# tuch-tara-smd.net
KiCad netlist of a schematic drawn in Altium Designer
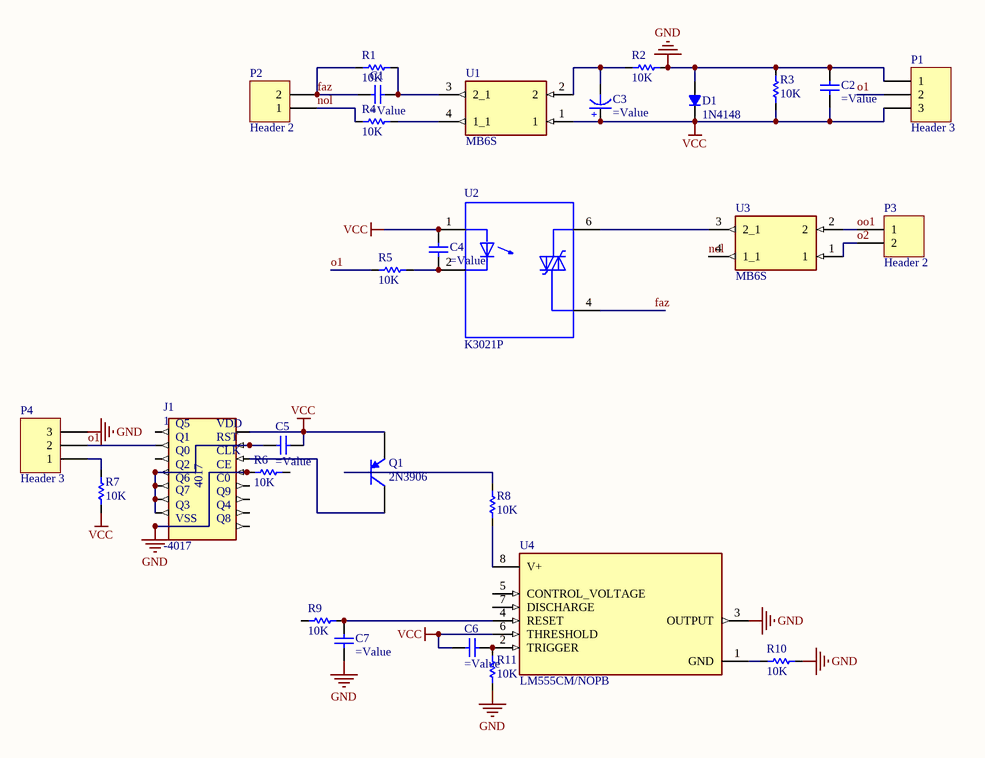
[diagram p0: tuch-tara-smd.SchDoc]

(export (version "E")
  (design (tool "Eeschema 10.0.6"))
  (components
    (comp (ref "C1")
      (value "~")
      (footprint "CAP-30")
      (description "Capacitor")
      (libsource (lib "AltiumLib1") (part "Capacitor"))
    )
    (comp (ref "C2")
      (value "~")
      (footprint "CAP 1206")
      (description "Capacitor")
      (libsource (lib "AltiumLib1") (part "Capacitor"))
    )
    (comp (ref "C3")
      (value "~")
      (footprint "ELEC-CAP-RAD10-20")
      (description "Electrolytic Capacitor")
      (libsource (lib "AltiumLib1") (part "Capacitor Electrolytic"))
    )
    (comp (ref "C4")
      (value "~")
      (footprint "CAP 1206")
      (description "Capacitor")
      (libsource (lib "AltiumLib1") (part "Capacitor"))
    )
    (comp (ref "C5")
      (value "~")
      (footprint "CAP 1206")
      (description "Capacitor")
      (libsource (lib "AltiumLib1") (part "Capacitor"))
    )
    (comp (ref "C6")
      (value "~")
      (footprint "CAP 1206")
      (description "Capacitor")
      (libsource (lib "AltiumLib1") (part "Capacitor"))
    )
    (comp (ref "C7")
      (value "~")
      (footprint "CAP 1206")
      (description "Capacitor")
      (libsource (lib "AltiumLib1") (part "Capacitor"))
    )
    (comp (ref "D1")
      (value "MODEL")
      (footprint "DO-41")
      (description "Diode")
      (fields (field (name "MODEL") "1N4148"))
      (libsource (lib "AltiumLib1") (part "Diode"))
    )
    (comp (ref "J1")
      (value "-4017")
      (footprint "SOIC127P600X175-16N")
      (description "10000pF Â±1% 25V Ceramic Capacitor C0G, NP0 0603 (1608 Metric)")
      (fields (field (name "MF") "Heyco") (field (name "MP") "4017"))
      (libsource (lib "-4017") (part "-4017"))
    )
    (comp (ref "P1")
      (value "Header 3")
      (footprint "HDR1X3")
      (description "Header, 3-Pin")
      (fields (field (name "PUBLISHER") "Altium Limited"))
      (libsource (lib "") (part "Header 3_1"))
    )
    (comp (ref "P2")
      (value "Header 2")
      (footprint "HDR1X2")
      (description "Header, 2-Pin")
      (fields (field (name "PUBLISHER") "Altium Limited"))
      (libsource (lib "") (part "Header 2_1"))
    )
    (comp (ref "P3")
      (value "Header 2")
      (footprint "HDR1X2")
      (description "Header, 2-Pin")
      (fields (field (name "PUBLISHER") "Altium Limited"))
      (libsource (lib "Miscellaneous Connectors") (part "Header 2"))
    )
    (comp (ref "P4")
      (value "Header 3")
      (footprint "HDR1X3")
      (description "Header, 3-Pin")
      (fields (field (name "PUBLISHER") "Altium Limited"))
      (libsource (lib "Miscellaneous Connectors") (part "Header 3"))
    )
    (comp (ref "Q1")
      (value "2N3906")
      (footprint "MMBT3904-TP:SOT23-3")
      (description "PNP General Purpose Amplifier")
      (fields (field (name "PUBLISHER") "Altium Limited"))
      (libsource (lib "Miscellaneous Devices") (part "2N3906"))
    )
    (comp (ref "R1")
      (value "10K")
      (footprint "RES 1206 (3216X08L)")
      (description "Resistor")
      (fields (field (name "TOLERANCE") "5%") (field (name "POWER") "1/4 W"))
      (libsource (lib "AltiumLib1") (part "Resistor"))
    )
    (comp (ref "R2")
      (value "10K")
      (footprint "RES 1206 (3216X08L)")
      (description "Resistor")
      (fields (field (name "TOLERANCE") "5%") (field (name "POWER") "1/4 W"))
      (libsource (lib "AltiumLib1") (part "Resistor"))
    )
    (comp (ref "R3")
      (value "10K")
      (footprint "RES 1206 (3216X08L)")
      (description "Resistor")
      (fields (field (name "TOLERANCE") "5%") (field (name "POWER") "1/4 W"))
      (libsource (lib "AltiumLib1") (part "Resistor"))
    )
    (comp (ref "R4")
      (value "10K")
      (footprint "RES 2512 (6331X07L)")
      (description "Resistor")
      (fields (field (name "TOLERANCE") "5%") (field (name "POWER") "1/4 W"))
      (libsource (lib "AltiumLib1") (part "Resistor"))
    )
    (comp (ref "R5")
      (value "10K")
      (footprint "RES 1206 (3216X08L)")
      (description "Resistor")
      (fields (field (name "TOLERANCE") "5%") (field (name "POWER") "1/4 W"))
      (libsource (lib "AltiumLib1") (part "Resistor"))
    )
    (comp (ref "R6")
      (value "10K")
      (footprint "RES 1206 (3216X08L)")
      (description "Resistor")
      (fields (field (name "TOLERANCE") "5%") (field (name "POWER") "1/4 W"))
      (libsource (lib "AltiumLib1") (part "Resistor"))
    )
    (comp (ref "R7")
      (value "10K")
      (footprint "Res-(1/4)")
      (description "Resistor")
      (fields (field (name "TOLERANCE") "5%") (field (name "POWER") "1/4 W"))
      (libsource (lib "AltiumLib1") (part "Resistor"))
    )
    (comp (ref "R8")
      (value "10K")
      (footprint "RES 1206 (3216X08L)")
      (description "Resistor")
      (fields (field (name "TOLERANCE") "5%") (field (name "POWER") "1/4 W"))
      (libsource (lib "AltiumLib1") (part "Resistor"))
    )
    (comp (ref "R9")
      (value "10K")
      (footprint "RES 1206 (3216X08L)")
      (description "Resistor")
      (fields (field (name "TOLERANCE") "5%") (field (name "POWER") "1/4 W"))
      (libsource (lib "AltiumLib1") (part "Resistor"))
    )
    (comp (ref "R10")
      (value "10K")
      (footprint "RES 1206 (3216X08L)")
      (description "Resistor")
      (fields (field (name "TOLERANCE") "5%") (field (name "POWER") "1/4 W"))
      (libsource (lib "AltiumLib1") (part "Resistor"))
    )
    (comp (ref "R11")
      (value "10K")
      (footprint "RES 1206 (3216X08L)")
      (description "Resistor")
      (fields (field (name "TOLERANCE") "5%") (field (name "POWER") "1/4 W"))
      (libsource (lib "AltiumLib1") (part "Resistor"))
    )
    (comp (ref "U1")
      (value "MB6S")
      (footprint "SOIC245P670X270-4N")
      (description "Bridge Rectifier Single Phase Standard 600V Surface Mount 4-SOIC")
      (fields (field (name "MF") "ON Semiconductor") (field (name "DIGI-KEY_PART_NUMBER") "MB6SCT-ND"))
      (libsource (lib "MB6S") (part "MB6S"))
    )
    (comp (ref "U2")
      (value "K3021P")
      (footprint "DIP762W50P254L730H410Q6")
      (description "Optoisolator Triac Output 5300Vrms 1 Channel 6-DIP")
      (fields (field (name "MF") "Vishay Semiconductor"))
      (libsource (lib "K3021P") (part "K3021P"))
    )
    (comp (ref "U3")
      (value "MB6S")
      (footprint "SOIC245P670X270-4N")
      (description "Bridge Rectifier Single Phase Standard 600V Surface Mount 4-SOIC")
      (fields (field (name "MF") "ON Semiconductor") (field (name "DIGI-KEY_PART_NUMBER") "MB6SCT-ND"))
      (libsource (lib "MB6S") (part "MB6S"))
    )
    (comp (ref "U4")
      (value "LM555CM/NOPB")
      (footprint "SOIC127P599X175-8N")
      (description "Highly Stable 555 Timer 8-SOIC 0 to 70")
      (libsource (lib "LM555CM_NOPB") (part "LM555CM/NOPB"))
    )
  )
  (nets
    (net (code "1") (name "/faz") (class "Default")
      (node (ref "C1") (pin "1") (pinfunction "+_1") (pintype "passive"))
      (node (ref "P2") (pin "2") (pinfunction "2_2") (pintype "passive"))
      (node (ref "R1") (pin "2") (pinfunction "2_2") (pintype "passive"))
      (node (ref "U2") (pin "4") (pinfunction "MT1_4") (pintype "passive"))
    )
    (net (code "2") (name "/nol") (class "Default")
      (node (ref "P2") (pin "1") (pinfunction "1_1") (pintype "passive"))
      (node (ref "R4") (pin "2") (pinfunction "2_2") (pintype "passive"))
      (node (ref "U3") (pin "4") (pinfunction "1_1_4") (pintype "output"))
    )
    (net (code "3") (name "/o1") (class "Default")
      (node (ref "J1") (pin "2") (pinfunction "Q1_2") (pintype "output"))
      (node (ref "P1") (pin "2") (pinfunction "2_2") (pintype "passive"))
      (node (ref "P4") (pin "2") (pinfunction "2_2") (pintype "passive"))
      (node (ref "R5") (pin "1") (pinfunction "1_1") (pintype "passive"))
    )
    (net (code "4") (name "/o2") (class "Default")
      (node (ref "P3") (pin "2") (pinfunction "2_2") (pintype "passive"))
      (node (ref "U3") (pin "1") (pinfunction "1_1") (pintype "input"))
    )
    (net (code "5") (name "/oo1") (class "Default")
      (node (ref "P3") (pin "1") (pinfunction "1_1") (pintype "passive"))
      (node (ref "U3") (pin "2") (pinfunction "2_2") (pintype "input"))
    )
    (net (code "6") (name "GND") (class "Default")
      (node (ref "C2") (pin "2") (pinfunction "-_2") (pintype "passive"))
      (node (ref "C7") (pin "2") (pinfunction "-_2") (pintype "passive"))
      (node (ref "D1") (pin "1") (pinfunction "A_1") (pintype "passive"))
      (node (ref "J1") (pin "13") (pinfunction "CE_13") (pintype "input"))
      (node (ref "J1") (pin "8") (pinfunction "VSS_8") (pintype "power_in"))
      (node (ref "P1") (pin "1") (pinfunction "1_1") (pintype "passive"))
      (node (ref "P4") (pin "3") (pinfunction "3_3") (pintype "passive"))
      (node (ref "R10") (pin "2") (pinfunction "2_2") (pintype "passive"))
      (node (ref "R11") (pin "1") (pinfunction "1_1") (pintype "passive"))
      (node (ref "R2") (pin "2") (pinfunction "2_2") (pintype "passive"))
      (node (ref "R3") (pin "2") (pinfunction "2_2") (pintype "passive"))
      (node (ref "R6") (pin "1") (pinfunction "1_1") (pintype "passive"))
      (node (ref "U4") (pin "3") (pinfunction "OUTPUT_3") (pintype "output"))
    )
    (net (code "7") (name "Net-(C1--)") (class "Default")
      (node (ref "C1") (pin "2") (pinfunction "-_2") (pintype "passive"))
      (node (ref "R1") (pin "1") (pinfunction "1_1") (pintype "passive"))
      (node (ref "U1") (pin "3") (pinfunction "2_1_3") (pintype "output"))
    )
    (net (code "8") (name "Net-(C3--)") (class "Default")
      (node (ref "C3") (pin "1") (pinfunction "-_1") (pintype "passive"))
      (node (ref "R2") (pin "1") (pinfunction "1_1") (pintype "passive"))
      (node (ref "U1") (pin "2") (pinfunction "2_2") (pintype "input"))
    )
    (net (code "9") (name "Net-(C4-+)") (class "Default")
      (node (ref "C4") (pin "1") (pinfunction "+_1") (pintype "passive"))
      (node (ref "R5") (pin "2") (pinfunction "2_2") (pintype "passive"))
      (node (ref "U2") (pin "2") (pinfunction "C_2") (pintype "passive"))
    )
    (net (code "10") (name "Net-(C5--)") (class "Default")
      (node (ref "C5") (pin "2") (pinfunction "-_2") (pintype "passive"))
      (node (ref "J1") (pin "15") (pinfunction "RST_15") (pintype "input"))
      (node (ref "J1") (pin "4") (pinfunction "Q2_4") (pintype "output"))
      (node (ref "J1") (pin "5") (pinfunction "Q6_5") (pintype "output"))
      (node (ref "J1") (pin "6") (pinfunction "Q7_6") (pintype "output"))
      (node (ref "J1") (pin "7") (pinfunction "Q3_7") (pintype "output"))
    )
    (net (code "11") (name "Net-(C6-+)") (class "Default")
      (node (ref "C6") (pin "1") (pinfunction "+_1") (pintype "passive"))
      (node (ref "R11") (pin "2") (pinfunction "2_2") (pintype "passive"))
      (node (ref "U4") (pin "2") (pinfunction "TRIGGER_2") (pintype "input"))
    )
    (net (code "12") (name "Net-(C7-+)") (class "Default")
      (node (ref "C7") (pin "1") (pinfunction "+_1") (pintype "passive"))
      (node (ref "R9") (pin "2") (pinfunction "2_2") (pintype "passive"))
      (node (ref "U4") (pin "4") (pinfunction "RESET_4") (pintype "input"))
    )
    (net (code "13") (name "Net-(J1-CLK)") (class "Default")
      (node (ref "J1") (pin "14") (pinfunction "CLK_14") (pintype "input"))
      (node (ref "Q1") (pin "3") (pinfunction "C_3") (pintype "passive"))
    )
    (net (code "14") (name "Net-(P4-Pad1)") (class "Default")
      (node (ref "P4") (pin "1") (pinfunction "1_1") (pintype "passive"))
      (node (ref "R7") (pin "2") (pinfunction "2_2") (pintype "passive"))
    )
    (net (code "15") (name "Net-(Q1-B)") (class "Default")
      (node (ref "Q1") (pin "2") (pinfunction "B_2") (pintype "passive"))
      (node (ref "R8") (pin "2") (pinfunction "2_2") (pintype "passive"))
    )
    (net (code "16") (name "Net-(U1-1_1)") (class "Default")
      (node (ref "R4") (pin "1") (pinfunction "1_1") (pintype "passive"))
      (node (ref "U1") (pin "4") (pinfunction "1_1_4") (pintype "output"))
    )
    (net (code "17") (name "Net-(U2-MT2)") (class "Default")
      (node (ref "U2") (pin "6") (pinfunction "MT2_6") (pintype "passive"))
      (node (ref "U3") (pin "3") (pinfunction "2_1_3") (pintype "output"))
    )
    (net (code "18") (name "Net-(U4-GND)") (class "Default")
      (node (ref "R10") (pin "1") (pinfunction "1_1") (pintype "passive"))
      (node (ref "U4") (pin "1") (pinfunction "GND_1") (pintype "power_in"))
    )
    (net (code "19") (name "Net-(U4-V+)") (class "Default")
      (node (ref "R8") (pin "1") (pinfunction "1_1") (pintype "passive"))
      (node (ref "U4") (pin "8") (pinfunction "V+_8") (pintype "power_in"))
    )
    (net (code "20") (name "VCC") (class "Default")
      (node (ref "C2") (pin "1") (pinfunction "+_1") (pintype "passive"))
      (node (ref "C3") (pin "2") (pinfunction "+_2") (pintype "passive"))
      (node (ref "C4") (pin "2") (pinfunction "-_2") (pintype "passive"))
      (node (ref "C5") (pin "1") (pinfunction "+_1") (pintype "passive"))
      (node (ref "C6") (pin "2") (pinfunction "-_2") (pintype "passive"))
      (node (ref "D1") (pin "2") (pinfunction "K_2") (pintype "passive"))
      (node (ref "J1") (pin "16") (pinfunction "VDD_16") (pintype "power_in"))
      (node (ref "P1") (pin "3") (pinfunction "3_3") (pintype "passive"))
      (node (ref "Q1") (pin "1") (pinfunction "E_1") (pintype "passive"))
      (node (ref "R3") (pin "1") (pinfunction "1_1") (pintype "passive"))
      (node (ref "R7") (pin "1") (pinfunction "1_1") (pintype "passive"))
      (node (ref "U1") (pin "1") (pinfunction "1_1") (pintype "input"))
      (node (ref "U2") (pin "1") (pinfunction "A_1") (pintype "passive"))
      (node (ref "U4") (pin "6") (pinfunction "THRESHOLD_6") (pintype "input"))
    )
    (net (code "21") (name "unconnected-(J1-C0-Pad12)") (class "Default")
      (node (ref "J1") (pin "12") (pinfunction "C0_12") (pintype "output"))
    )
    (net (code "22") (name "unconnected-(J1-Q0-Pad3)") (class "Default")
      (node (ref "J1") (pin "3") (pinfunction "Q0_3") (pintype "output"))
    )
    (net (code "23") (name "unconnected-(J1-Q4-Pad10)") (class "Default")
      (node (ref "J1") (pin "10") (pinfunction "Q4_10") (pintype "output"))
    )
    (net (code "24") (name "unconnected-(J1-Q5-Pad1)") (class "Default")
      (node (ref "J1") (pin "1") (pinfunction "Q5_1") (pintype "output"))
    )
    (net (code "25") (name "unconnected-(J1-Q8-Pad9)") (class "Default")
      (node (ref "J1") (pin "9") (pinfunction "Q8_9") (pintype "output"))
    )
    (net (code "26") (name "unconnected-(J1-Q9-Pad11)") (class "Default")
      (node (ref "J1") (pin "11") (pinfunction "Q9_11") (pintype "output"))
    )
    (net (code "27") (name "unconnected-(R6-Pad2)") (class "Default")
      (node (ref "R6") (pin "2") (pinfunction "2_2") (pintype "passive"))
    )
    (net (code "28") (name "unconnected-(R9-Pad1)") (class "Default")
      (node (ref "R9") (pin "1") (pinfunction "1_1") (pintype "passive"))
    )
    (net (code "29") (name "unconnected-(U4-CONTROL_VOLTAGE-Pad5)") (class "Default")
      (node (ref "U4") (pin "5") (pinfunction "CONTROL_VOLTAGE_5") (pintype "input"))
    )
    (net (code "30") (name "unconnected-(U4-DISCHARGE-Pad7)") (class "Default")
      (node (ref "U4") (pin "7") (pinfunction "DISCHARGE_7") (pintype "input"))
    )
  )
)
